# camera.net
KiCad netlist of a schematic drawn in Altium Designer
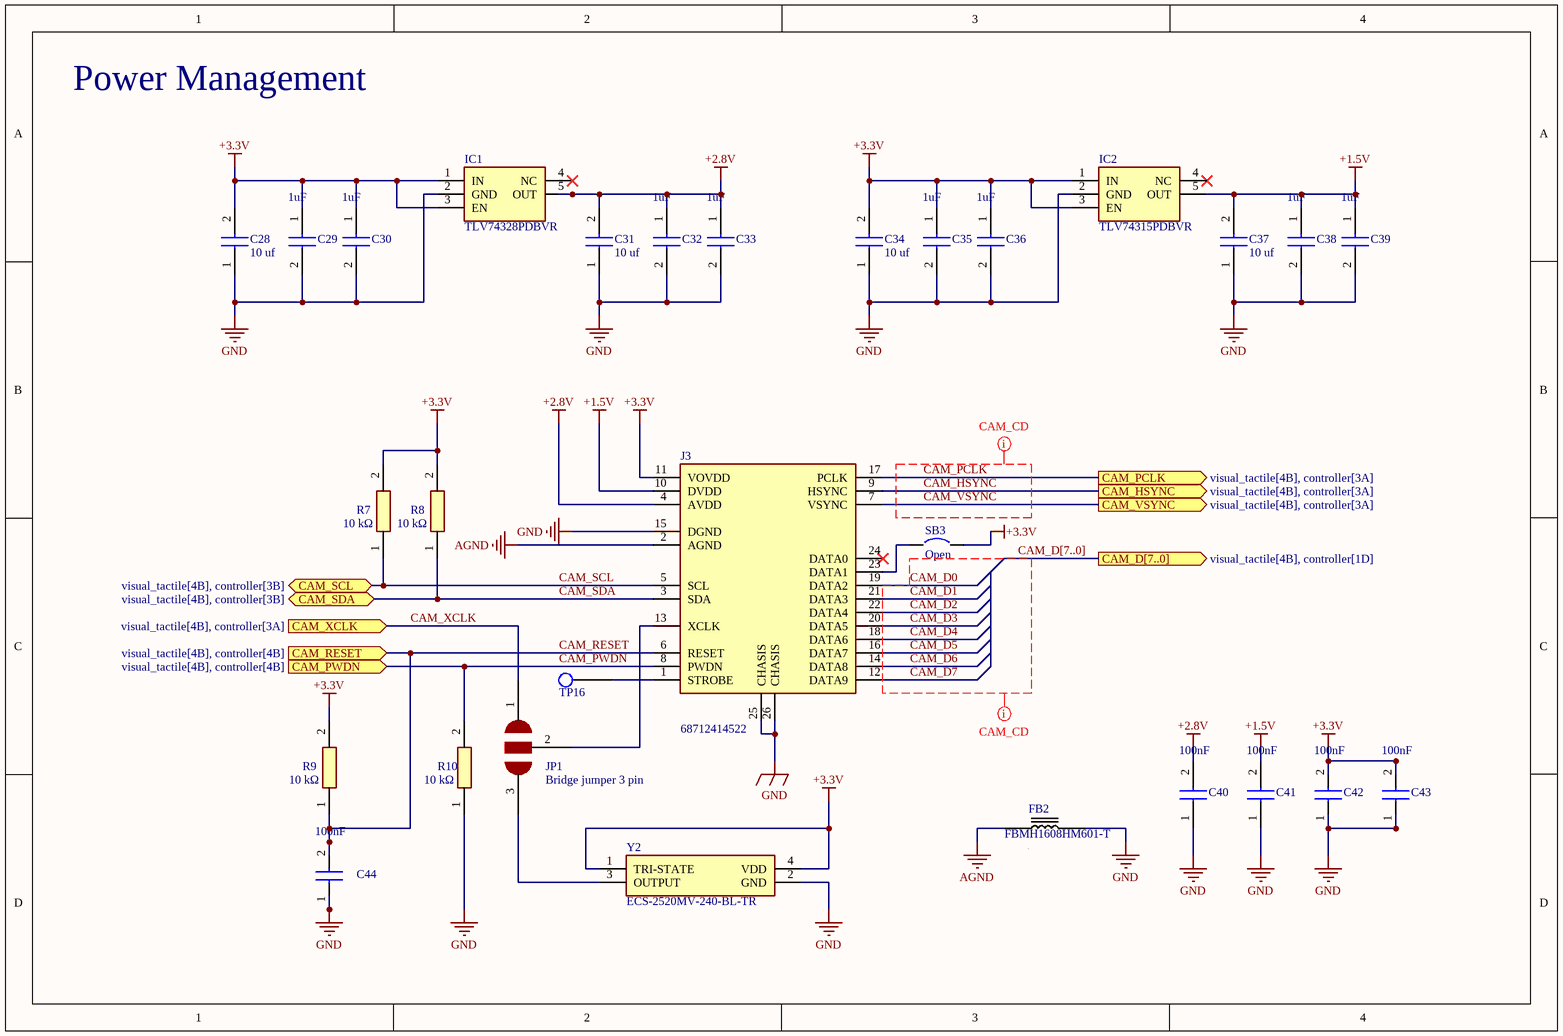
[diagram p0: camera.SchDoc]

(export (version "E")
  (design (tool "Eeschema 10.0.6"))
  (components
    (comp (ref "C28")
      (value "10 uf")
      (footprint "PCB_library:CAPC1608X87N")
      (fields
        (field (name "MANUFACTURER_PART_NUMBER") "C0603C300J5GACTU")
        (field (name "MOUSER PART NUMBER") "80-C0603C300J5G")
        (field (name "MANUFACTURER") "KEMET")
      )
      (libsource (lib "*") (part "C0603C300J5GACTU"))
    )
    (comp (ref "C29")
      (value "1uF")
      (footprint "PCB_library:CAPC1608X87N")
      (fields
        (field (name "MANUFACTURER_PART_NUMBER") "C0603C300J5GACTU")
        (field (name "MOUSER PART NUMBER") "80-C0603C300J5G")
        (field (name "MANUFACTURER") "Kyocera AVX")
      )
      (libsource (lib "PCB_library") (part "C0603C300J5GACTU"))
    )
    (comp (ref "C30")
      (value "1uF")
      (footprint "PCB_library:CAPC1608X87N")
      (fields
        (field (name "MANUFACTURER_PART_NUMBER") "C0603C300J5GACTU")
        (field (name "MOUSER PART NUMBER") "80-C0603C300J5G")
        (field (name "MANUFACTURER") "Kyocera AVX")
      )
      (libsource (lib "PCB_library") (part "C0603C300J5GACTU"))
    )
    (comp (ref "C31")
      (value "10 uf")
      (footprint "PCB_library:CAPC1608X87N")
      (fields
        (field (name "MANUFACTURER_PART_NUMBER") "C0603C300J5GACTU")
        (field (name "MOUSER PART NUMBER") "80-C0603C300J5G")
        (field (name "MANUFACTURER") "KEMET")
      )
      (libsource (lib "*") (part "C0603C300J5GACTU"))
    )
    (comp (ref "C32")
      (value "1uF")
      (footprint "PCB_library:CAPC1608X87N")
      (fields
        (field (name "MANUFACTURER_PART_NUMBER") "C0603C300J5GACTU")
        (field (name "MOUSER PART NUMBER") "80-C0603C300J5G")
        (field (name "MANUFACTURER") "Kyocera AVX")
      )
      (libsource (lib "PCB_library") (part "C0603C300J5GACTU"))
    )
    (comp (ref "C33")
      (value "1uF")
      (footprint "PCB_library:CAPC1608X87N")
      (fields
        (field (name "MANUFACTURER_PART_NUMBER") "C0603C300J5GACTU")
        (field (name "MOUSER PART NUMBER") "80-C0603C300J5G")
        (field (name "MANUFACTURER") "Kyocera AVX")
      )
      (libsource (lib "PCB_library") (part "C0603C300J5GACTU"))
    )
    (comp (ref "C34")
      (value "10 uf")
      (footprint "PCB_library:CAPC1608X87N")
      (fields
        (field (name "MANUFACTURER_PART_NUMBER") "C0603C300J5GACTU")
        (field (name "MOUSER PART NUMBER") "80-C0603C300J5G")
        (field (name "MANUFACTURER") "KEMET")
      )
      (libsource (lib "*") (part "C0603C300J5GACTU"))
    )
    (comp (ref "C35")
      (value "1uF")
      (footprint "PCB_library:CAPC1608X87N")
      (fields
        (field (name "MANUFACTURER_PART_NUMBER") "C0603C300J5GACTU")
        (field (name "MOUSER PART NUMBER") "80-C0603C300J5G")
        (field (name "MANUFACTURER") "Kyocera AVX")
      )
      (libsource (lib "PCB_library") (part "C0603C300J5GACTU"))
    )
    (comp (ref "C36")
      (value "1uF")
      (footprint "PCB_library:CAPC1608X87N")
      (fields
        (field (name "MANUFACTURER_PART_NUMBER") "C0603C300J5GACTU")
        (field (name "MOUSER PART NUMBER") "80-C0603C300J5G")
        (field (name "MANUFACTURER") "Kyocera AVX")
      )
      (libsource (lib "PCB_library") (part "C0603C300J5GACTU"))
    )
    (comp (ref "C37")
      (value "10 uf")
      (footprint "PCB_library:CAPC1608X87N")
      (fields
        (field (name "MANUFACTURER_PART_NUMBER") "C0603C300J5GACTU")
        (field (name "MOUSER PART NUMBER") "80-C0603C300J5G")
        (field (name "MANUFACTURER") "KEMET")
      )
      (libsource (lib "*") (part "C0603C300J5GACTU"))
    )
    (comp (ref "C38")
      (value "1uF")
      (footprint "PCB_library:CAPC1608X87N")
      (fields
        (field (name "MANUFACTURER_PART_NUMBER") "C0603C300J5GACTU")
        (field (name "MOUSER PART NUMBER") "80-C0603C300J5G")
        (field (name "MANUFACTURER") "Kyocera AVX")
      )
      (libsource (lib "PCB_library") (part "C0603C300J5GACTU"))
    )
    (comp (ref "C39")
      (value "1uF")
      (footprint "PCB_library:CAPC1608X87N")
      (fields
        (field (name "MANUFACTURER_PART_NUMBER") "C0603C300J5GACTU")
        (field (name "MOUSER PART NUMBER") "80-C0603C300J5G")
        (field (name "MANUFACTURER") "Kyocera AVX")
      )
      (libsource (lib "PCB_library") (part "C0603C300J5GACTU"))
    )
    (comp (ref "C40")
      (value "100nF")
      (footprint "PCB_library:CAPC1608X87N")
      (fields
        (field (name "MANUFACTURER_PART_NUMBER") "C0603C300J5GACTU")
        (field (name "MOUSER PART NUMBER") "80-C0603C300J5G")
        (field (name "MANUFACTURER") "TDK")
      )
      (libsource (lib "PCB_library") (part "C0603C300J5GACTU"))
    )
    (comp (ref "C41")
      (value "100nF")
      (footprint "PCB_library:CAPC1608X87N")
      (fields
        (field (name "MANUFACTURER_PART_NUMBER") "C0603C300J5GACTU")
        (field (name "MOUSER PART NUMBER") "80-C0603C300J5G")
        (field (name "MANUFACTURER") "TDK")
      )
      (libsource (lib "PCB_library") (part "C0603C300J5GACTU"))
    )
    (comp (ref "C42")
      (value "100nF")
      (footprint "PCB_library:CAPC1608X87N")
      (fields
        (field (name "MANUFACTURER_PART_NUMBER") "C0603C300J5GACTU")
        (field (name "MOUSER PART NUMBER") "80-C0603C300J5G")
        (field (name "MANUFACTURER") "TDK")
      )
      (libsource (lib "PCB_library") (part "C0603C300J5GACTU"))
    )
    (comp (ref "C43")
      (value "100nF")
      (footprint "PCB_library:CAPC1608X87N")
      (fields
        (field (name "MANUFACTURER_PART_NUMBER") "C0603C300J5GACTU")
        (field (name "MOUSER PART NUMBER") "80-C0603C300J5G")
        (field (name "MANUFACTURER") "TDK")
      )
      (libsource (lib "PCB_library") (part "C0603C300J5GACTU"))
    )
    (comp (ref "C44")
      (value "100nF")
      (footprint "PCB_library:CAPC1608X87N")
      (fields
        (field (name "MANUFACTURER_PART_NUMBER") "C0603C300J5GACTU")
        (field (name "MOUSER PART NUMBER") "80-C0603C300J5G")
        (field (name "MANUFACTURER") "TDK")
      )
      (libsource (lib "PCB_library") (part "C0603C300J5GACTU"))
    )
    (comp (ref "FB2")
      (value "FBMH1608HM601-T")
      (footprint "PCB_library:BEADC1608X90N")
      (description "Ferrite Bead")
      (fields (field (name "MOUSER PART NUMBER") "963-FBMH1608HM601-T"))
      (libsource (lib "PCB_library") (part "FBMH1608HM601-T"))
    )
    (comp (ref "IC1")
      (value "TLV74328PDBVR")
      (footprint "PCB_library:SOT95P280X145-5N")
      (description "Integrated Circuit")
      (fields (field (name "MOUSER PART NUMBER") "595-TLV74328PDBVR"))
      (libsource (lib "*") (part "TLV74328PDBVR"))
    )
    (comp (ref "IC2")
      (value "TLV74315PDBVR")
      (footprint "PCB_library:SOT95P280X145-5N")
      (description "Integrated Circuit")
      (fields (field (name "MOUSER PART NUMBER") "595-TLV74315PDBVR"))
      (libsource (lib "*") (part "TLV74315PDBVR"))
    )
    (comp (ref "J3")
      (value "68712414522")
      (footprint "PCB_library:68712414522")
      (description "Connector")
      (fields (field (name "MOUSER PART NUMBER") "710-68712414522"))
      (libsource (lib "PCB_library") (part "68712414522"))
    )
    (comp (ref "JP1")
      (value "Bridge jumper 3 pin")
      (footprint "Bridge jumper 3 pin")
      (libsource (lib "PCB_library") (part "Bridge jumper 3 pin"))
    )
    (comp (ref "R7")
      (value "10 kΩ")
      (footprint "RESC1005X35N")
      (description "Resistor")
      (fields
        (field (name "MANUFACTURER_PART_NUMBER") "CPF0402B100KE")
        (field (name "MOUSER PART NUMBER") "279-CPF0402B100KE")
      )
      (libsource (lib "*") (part "CPF0402B100KE"))
    )
    (comp (ref "R8")
      (value "10 kΩ")
      (footprint "RESC1005X35N")
      (description "Resistor")
      (fields
        (field (name "MANUFACTURER_PART_NUMBER") "CPF0402B100KE")
        (field (name "MOUSER PART NUMBER") "279-CPF0402B100KE")
      )
      (libsource (lib "*") (part "CPF0402B100KE"))
    )
    (comp (ref "R9")
      (value "10 kΩ")
      (footprint "RESC1005X35N")
      (description "Resistor")
      (fields
        (field (name "MANUFACTURER_PART_NUMBER") "CPF0402B100KE")
        (field (name "MOUSER PART NUMBER") "279-CPF0402B100KE")
      )
      (libsource (lib "*") (part "CPF0402B100KE"))
    )
    (comp (ref "R10")
      (value "10 kΩ")
      (footprint "RESC1005X35N")
      (description "Resistor")
      (fields
        (field (name "MANUFACTURER_PART_NUMBER") "CPF0402B100KE")
        (field (name "MOUSER PART NUMBER") "279-CPF0402B100KE")
      )
      (libsource (lib "*") (part "CPF0402B100KE"))
    )
    (comp (ref "SB3")
      (value "Open")
      (footprint "SB_0603")
      (description "Circuit Breaker")
      (fields (field (name "PUBLISHER") "Altium Limited"))
      (libsource (lib "PCB_library") (part "Circuit Breaker"))
    )
    (comp (ref "TP16")
      (value "Test point")
      (footprint "test point")
      (libsource (lib "PCB_library") (part "Test point"))
    )
    (comp (ref "Y2")
      (value "ECS-2520MV-240-BL-TR")
      (footprint "PCB_library:ECS2520MV120BNTR")
      (description "Crystal or Oscillator")
      (fields
        (field (name "MANUFACTURER_PART_NUMBER") "ECS-2520MV-120-BN-TR")
        (field (name "MOUSER PART NUMBER") "520-2520MV-120-BN-T")
      )
      (libsource (lib "PCB_library") (part "ECS-2520MV-240-BL-TR"))
    )
  )
  (nets
    (net (code "1") (name "+1.5V") (class "Default")
      (node (ref "C37") (pin "2") (pinfunction "2_2") (pintype "passive"))
      (node (ref "C38") (pin "1") (pinfunction "1_1") (pintype "passive"))
      (node (ref "C39") (pin "1") (pinfunction "1_1") (pintype "passive"))
      (node (ref "C41") (pin "2") (pinfunction "2_2") (pintype "passive"))
      (node (ref "IC2") (pin "5") (pinfunction "OUT_5") (pintype "passive"))
      (node (ref "J3") (pin "10") (pinfunction "DVDD_10") (pintype "passive"))
    )
    (net (code "2") (name "+2.8V") (class "Default")
      (node (ref "C31") (pin "2") (pinfunction "2_2") (pintype "passive"))
      (node (ref "C32") (pin "1") (pinfunction "1_1") (pintype "passive"))
      (node (ref "C33") (pin "1") (pinfunction "1_1") (pintype "passive"))
      (node (ref "C40") (pin "2") (pinfunction "2_2") (pintype "passive"))
      (node (ref "IC1") (pin "5") (pinfunction "OUT_5") (pintype "passive"))
      (node (ref "J3") (pin "4") (pinfunction "AVDD_4") (pintype "passive"))
    )
    (net (code "3") (name "+3.3V") (class "Default")
      (node (ref "C28") (pin "2") (pinfunction "2_2") (pintype "passive"))
      (node (ref "C29") (pin "1") (pinfunction "1_1") (pintype "passive"))
      (node (ref "C30") (pin "1") (pinfunction "1_1") (pintype "passive"))
      (node (ref "C34") (pin "2") (pinfunction "2_2") (pintype "passive"))
      (node (ref "C35") (pin "1") (pinfunction "1_1") (pintype "passive"))
      (node (ref "C36") (pin "1") (pinfunction "1_1") (pintype "passive"))
      (node (ref "C42") (pin "2") (pinfunction "2_2") (pintype "passive"))
      (node (ref "C43") (pin "2") (pinfunction "2_2") (pintype "passive"))
      (node (ref "IC1") (pin "1") (pinfunction "IN_1") (pintype "passive"))
      (node (ref "IC1") (pin "3") (pinfunction "EN_3") (pintype "passive"))
      (node (ref "IC2") (pin "1") (pinfunction "IN_1") (pintype "passive"))
      (node (ref "IC2") (pin "3") (pinfunction "EN_3") (pintype "passive"))
      (node (ref "J3") (pin "11") (pinfunction "VOVDD_11") (pintype "passive"))
      (node (ref "R7") (pin "2") (pinfunction "2_2") (pintype "passive"))
      (node (ref "R8") (pin "2") (pinfunction "2_2") (pintype "passive"))
      (node (ref "R9") (pin "2") (pinfunction "2_2") (pintype "passive"))
      (node (ref "SB3") (pin "2") (pinfunction "2_2") (pintype "passive"))
      (node (ref "Y2") (pin "1") (pinfunction "TRI-STATE_1") (pintype "passive"))
      (node (ref "Y2") (pin "4") (pinfunction "VDD_4") (pintype "passive"))
    )
    (net (code "4") (name "/CAM_D0") (class "Default")
      (node (ref "J3") (pin "19") (pinfunction "DATA2_19") (pintype "passive"))
    )
    (net (code "5") (name "/CAM_D1") (class "Default")
      (node (ref "J3") (pin "21") (pinfunction "DATA3_21") (pintype "passive"))
    )
    (net (code "6") (name "/CAM_D2") (class "Default")
      (node (ref "J3") (pin "22") (pinfunction "DATA4_22") (pintype "passive"))
    )
    (net (code "7") (name "/CAM_D3") (class "Default")
      (node (ref "J3") (pin "20") (pinfunction "DATA5_20") (pintype "passive"))
    )
    (net (code "8") (name "/CAM_D4") (class "Default")
      (node (ref "J3") (pin "18") (pinfunction "DATA6_18") (pintype "passive"))
    )
    (net (code "9") (name "/CAM_D5") (class "Default")
      (node (ref "J3") (pin "16") (pinfunction "DATA7_16") (pintype "passive"))
    )
    (net (code "10") (name "/CAM_D6") (class "Default")
      (node (ref "J3") (pin "14") (pinfunction "DATA8_14") (pintype "passive"))
    )
    (net (code "11") (name "/CAM_D7") (class "Default")
      (node (ref "J3") (pin "12") (pinfunction "DATA9_12") (pintype "passive"))
    )
    (net (code "13") (name "/CAM_HSYNC") (class "Default")
      (node (ref "J3") (pin "9") (pinfunction "HSYNC_9") (pintype "passive"))
    )
    (net (code "14") (name "/CAM_PCLK") (class "Default")
      (node (ref "J3") (pin "17") (pinfunction "PCLK_17") (pintype "passive"))
    )
    (net (code "15") (name "/CAM_PWDN") (class "Default")
      (node (ref "J3") (pin "8") (pinfunction "PWDN_8") (pintype "passive"))
      (node (ref "R10") (pin "2") (pinfunction "2_2") (pintype "passive"))
    )
    (net (code "16") (name "/CAM_RESET") (class "Default")
      (node (ref "C44") (pin "2") (pinfunction "2_2") (pintype "passive"))
      (node (ref "J3") (pin "6") (pinfunction "RESET_6") (pintype "passive"))
      (node (ref "R9") (pin "1") (pinfunction "1_1") (pintype "passive"))
    )
    (net (code "17") (name "/CAM_SCL") (class "Default")
      (node (ref "J3") (pin "5") (pinfunction "SCL_5") (pintype "passive"))
      (node (ref "R7") (pin "1") (pinfunction "1_1") (pintype "passive"))
    )
    (net (code "18") (name "/CAM_SDA") (class "Default")
      (node (ref "J3") (pin "3") (pinfunction "SDA_3") (pintype "passive"))
      (node (ref "R8") (pin "1") (pinfunction "1_1") (pintype "passive"))
    )
    (net (code "19") (name "/CAM_VSYNC") (class "Default")
      (node (ref "J3") (pin "7") (pinfunction "VSYNC_7") (pintype "passive"))
    )
    (net (code "20") (name "/CAM_XCLK") (class "Default")
      (node (ref "JP1") (pin "1") (pinfunction "1_1") (pintype "passive"))
    )
    (net (code "21") (name "AGND") (class "Default")
      (node (ref "FB2") (pin "1") (pinfunction "1_1") (pintype "passive"))
      (node (ref "J3") (pin "2") (pinfunction "AGND_2") (pintype "passive"))
    )
    (net (code "22") (name "GND") (class "Default")
      (node (ref "C28") (pin "1") (pinfunction "1_1") (pintype "passive"))
      (node (ref "C29") (pin "2") (pinfunction "2_2") (pintype "passive"))
      (node (ref "C30") (pin "2") (pinfunction "2_2") (pintype "passive"))
      (node (ref "C31") (pin "1") (pinfunction "1_1") (pintype "passive"))
      (node (ref "C32") (pin "2") (pinfunction "2_2") (pintype "passive"))
      (node (ref "C33") (pin "2") (pinfunction "2_2") (pintype "passive"))
      (node (ref "C34") (pin "1") (pinfunction "1_1") (pintype "passive"))
      (node (ref "C35") (pin "2") (pinfunction "2_2") (pintype "passive"))
      (node (ref "C36") (pin "2") (pinfunction "2_2") (pintype "passive"))
      (node (ref "C37") (pin "1") (pinfunction "1_1") (pintype "passive"))
      (node (ref "C38") (pin "2") (pinfunction "2_2") (pintype "passive"))
      (node (ref "C39") (pin "2") (pinfunction "2_2") (pintype "passive"))
      (node (ref "C40") (pin "1") (pinfunction "1_1") (pintype "passive"))
      (node (ref "C41") (pin "1") (pinfunction "1_1") (pintype "passive"))
      (node (ref "C42") (pin "1") (pinfunction "1_1") (pintype "passive"))
      (node (ref "C43") (pin "1") (pinfunction "1_1") (pintype "passive"))
      (node (ref "C44") (pin "1") (pinfunction "1_1") (pintype "passive"))
      (node (ref "FB2") (pin "2") (pinfunction "2_2") (pintype "passive"))
      (node (ref "IC1") (pin "2") (pinfunction "GND_2") (pintype "passive"))
      (node (ref "IC2") (pin "2") (pinfunction "GND_2") (pintype "passive"))
      (node (ref "J3") (pin "15") (pinfunction "DGND_15") (pintype "passive"))
      (node (ref "J3") (pin "25") (pinfunction "CHASIS_25") (pintype "passive"))
      (node (ref "J3") (pin "26") (pinfunction "CHASIS_26") (pintype "passive"))
      (node (ref "R10") (pin "1") (pinfunction "1_1") (pintype "passive"))
      (node (ref "Y2") (pin "2") (pinfunction "GND_2") (pintype "passive"))
    )
    (net (code "23") (name "Net-(J3-DATA1)") (class "Default")
      (node (ref "J3") (pin "23") (pinfunction "DATA1_23") (pintype "passive"))
      (node (ref "SB3") (pin "1") (pinfunction "1_1") (pintype "passive"))
    )
    (net (code "24") (name "Net-(J3-STROBE)") (class "Default")
      (node (ref "J3") (pin "1") (pinfunction "STROBE_1") (pintype "passive"))
      (node (ref "TP16") (pin "1") (pinfunction "1_1") (pintype "passive"))
    )
    (net (code "25") (name "Net-(J3-XCLK)") (class "Default")
      (node (ref "J3") (pin "13") (pinfunction "XCLK_13") (pintype "passive"))
      (node (ref "JP1") (pin "2") (pinfunction "2_2") (pintype "passive"))
    )
    (net (code "26") (name "Net-(Y2-OUTPUT)") (class "Default")
      (node (ref "JP1") (pin "3") (pinfunction "3_3") (pintype "passive"))
      (node (ref "Y2") (pin "3") (pinfunction "OUTPUT_3") (pintype "passive"))
    )
    (net (code "27") (name "unconnected-(IC1-NC-Pad4)") (class "Default")
      (node (ref "IC1") (pin "4") (pinfunction "NC_4") (pintype "passive+no_connect"))
    )
    (net (code "28") (name "unconnected-(IC2-NC-Pad4)") (class "Default")
      (node (ref "IC2") (pin "4") (pinfunction "NC_4") (pintype "passive+no_connect"))
    )
    (net (code "29") (name "unconnected-(J3-DATA0-Pad24)") (class "Default")
      (node (ref "J3") (pin "24") (pinfunction "DATA0_24") (pintype "passive+no_connect"))
    )
  )
)
